# coaches.net
KiCad netlist of a schematic drawn in EAGLE
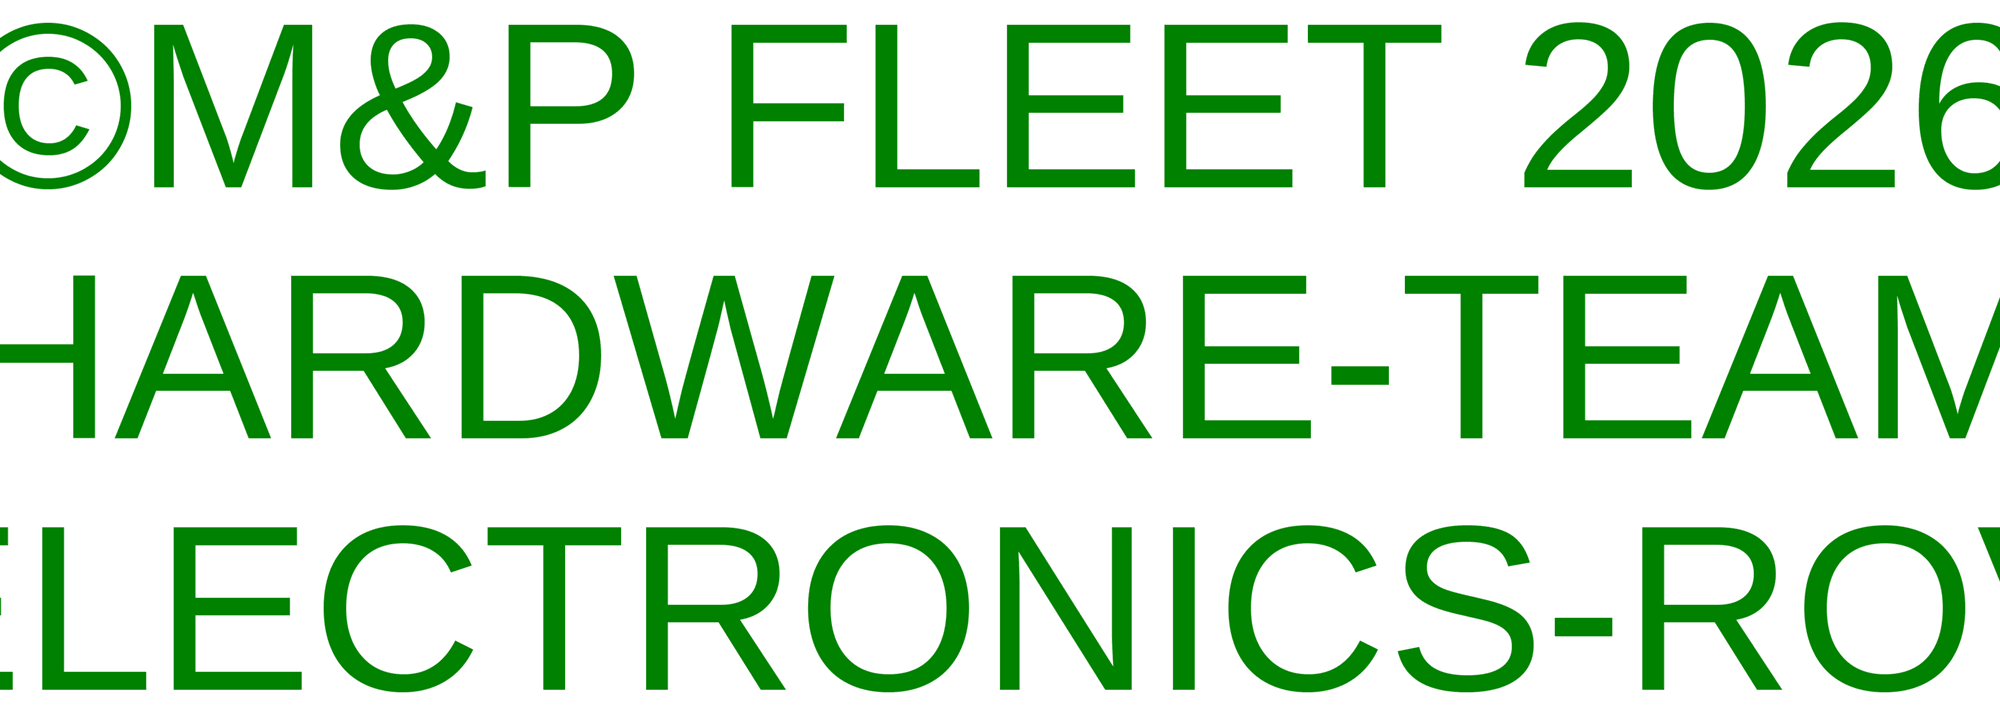
[diagram p0: schematic, sheet 1]
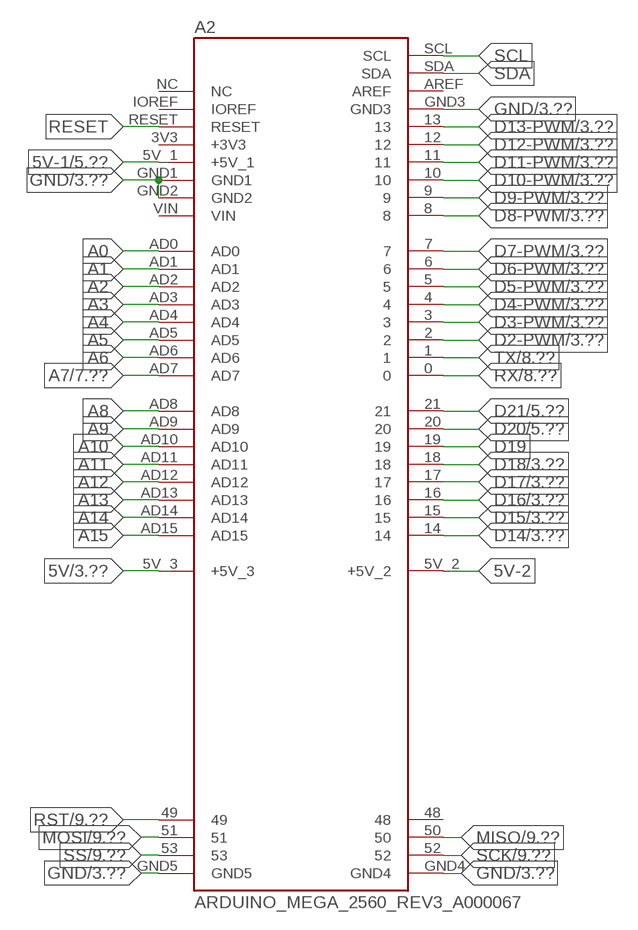
[diagram p1: schematic, sheet 2]
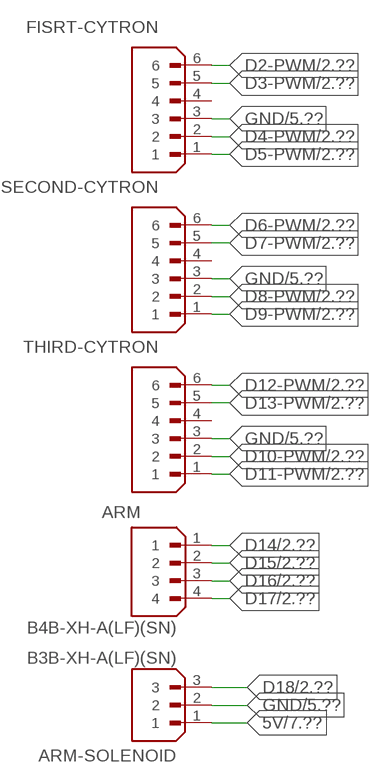
[diagram p2: schematic, sheet 3]
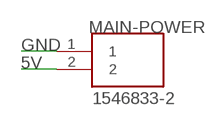
[diagram p3: schematic, sheet 4]
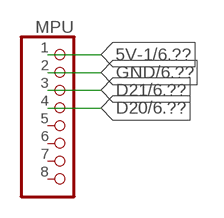
[diagram p4: schematic, sheet 5]
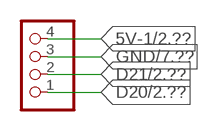
[diagram p5: schematic, sheet 6]
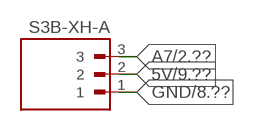
[diagram p6: schematic, sheet 7]
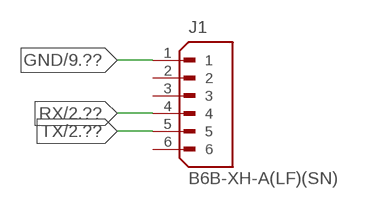
[diagram p7: schematic, sheet 8]
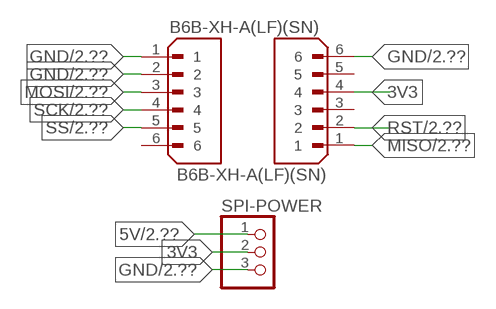
[diagram p8: schematic, sheet 9]

(export (version "E")
  (design (tool "Eeschema 10.0.6"))
  (components
    (comp (ref "A2")
      (value "ARDUINO_MEGA_2560_REV3_A000067")
      (footprint "eagle-import:ARDUINO_ARDUINO_MEGA_2560_REV3_A000067")
      (fields (field (name "MF") "Arduino") (field (name "MP") "ARDUINO MEGA 2560 REV3 | A000067"))
      (libsource (lib "eagle-import") (part "ARDUINO_MEGA_2560_REV3_A000067"))
    )
    (comp (ref "ARM")
      (value "B4B-XH-A(LF)(SN)")
      (footprint "eagle-import:JST_B4B-XH-A(LF)(SN)")
      (fields (field (name "MF") "JST Sales") (field (name "MP") "B4B-XH-A (LF)(SN)"))
      (libsource (lib "eagle-import") (part "B4B-XH-A(LF)(SN)"))
    )
    (comp (ref "ARM-SOLENOID")
      (value "B3B-XH-A(LF)(SN)")
      (footprint "eagle-import:JST_B3B-XH-A(LF)(SN)")
      (fields (field (name "MF") "JST Sales"))
      (libsource (lib "eagle-import") (part "B3B-XH-A(LF)(SN)"))
    )
    (comp (ref "FISRT-CYTRON")
      (value "B6B-XH-A(LF)(SN)")
      (footprint "eagle-import:JST_B6B-XH-A(LF)(SN)")
      (fields (field (name "MF") "JST Sales") (field (name "MP") "B6B-XH-A (LF)(SN)"))
      (libsource (lib "eagle-import") (part "data-cable(6-pin)_48447798_B6B-XH-A(LF)(SN)"))
    )
    (comp (ref "SECOND-CYTRON")
      (value "B6B-XH-A(LF)(SN)")
      (footprint "eagle-import:JST_B6B-XH-A(LF)(SN)")
      (fields (field (name "MF") "JST Sales") (field (name "MP") "B6B-XH-A (LF)(SN)"))
      (libsource (lib "eagle-import") (part "data-cable(6-pin)_48447798_B6B-XH-A(LF)(SN)"))
    )
    (comp (ref "THIRD-CYTRON")
      (value "B6B-XH-A(LF)(SN)")
      (footprint "eagle-import:JST_B6B-XH-A(LF)(SN)")
      (fields (field (name "MF") "JST Sales") (field (name "MP") "B6B-XH-A (LF)(SN)"))
      (libsource (lib "eagle-import") (part "data-cable(6-pin)_48447798_B6B-XH-A(LF)(SN)"))
    )
    (comp (ref "J2")
      (value "B6B-XH-A(LF)(SN)")
      (footprint "eagle-import:JST_B6B-XH-A(LF)(SN)")
      (fields (field (name "MF") "JST Sales") (field (name "MP") "B6B-XH-A (LF)(SN)"))
      (libsource (lib "eagle-import") (part "B6B-XH-A(LF)(SN)"))
    )
    (comp (ref "J4")
      (value "B6B-XH-A(LF)(SN)")
      (footprint "eagle-import:JST_B6B-XH-A(LF)(SN)")
      (fields (field (name "MF") "JST Sales") (field (name "MP") "B6B-XH-A (LF)(SN)"))
      (libsource (lib "eagle-import") (part "B6B-XH-A(LF)(SN)"))
    )
    (comp (ref "SPI-POWER")
      (value "PINHD-1X3")
      (footprint "eagle-import:1X03")
      (libsource (lib "eagle-import") (part "PINHD-1X3"))
    )
    (comp (ref "PROMETER")
      (value "PINHD-1X4")
      (footprint "eagle-import:1X04")
      (libsource (lib "eagle-import") (part "PINHD-1X4"))
    )
    (comp (ref "MAIN-POWER")
      (value "1546833-2")
      (footprint "eagle-import:TE_1546833-2")
      (fields (field (name "MF") "TE Connectivity"))
      (libsource (lib "eagle-import") (part "1546833-2"))
    )
    (comp (ref "J3")
      (value "S3B-XH-A")
      (footprint "eagle-import:JST_S3B-XH-A")
      (fields (field (name "MF") "JST"))
      (libsource (lib "eagle-import") (part "S3B-XH-A"))
    )
    (comp (ref "MPU")
      (value "PINHD-1X8")
      (footprint "eagle-import:1X08")
      (libsource (lib "eagle-import") (part "PINHD-1X8"))
    )
    (comp (ref "J1")
      (value "B6B-XH-A(LF)(SN)")
      (footprint "eagle-import:JST_B6B-XH-A(LF)(SN)")
      (fields (field (name "MF") "JST Sales") (field (name "MP") "B6B-XH-A (LF)(SN)"))
      (libsource (lib "eagle-import") (part "data-cable(6-pin)_48447798_B6B-XH-A(LF)(SN)"))
    )
  )
  (nets
    (net (code "1") (name "3V3") (class "Default")
      (node (ref "J4") (pin "4") (pinfunction "4_4") (pintype "passive"))
      (node (ref "SPI-POWER") (pin "2") (pinfunction "2_2") (pintype "passive"))
    )
    (net (code "2") (name "5V") (class "Default")
      (node (ref "A2") (pin "5V_3") (pinfunction "+5V_3_5V_3") (pintype "passive"))
      (node (ref "ARM-SOLENOID") (pin "1") (pinfunction "1_1") (pintype "passive"))
      (node (ref "J3") (pin "2") (pinfunction "2_2") (pintype "passive"))
      (node (ref "MAIN-POWER") (pin "2") (pinfunction "2_2") (pintype "passive"))
      (node (ref "SPI-POWER") (pin "1") (pinfunction "1_1") (pintype "passive"))
    )
    (net (code "3") (name "5V-1") (class "Default")
      (node (ref "A2") (pin "5V_1") (pinfunction "+5V_1_5V_1") (pintype "passive"))
      (node (ref "MPU") (pin "1") (pinfunction "1_1") (pintype "passive"))
      (node (ref "PROMETER") (pin "4") (pinfunction "4_4") (pintype "passive"))
    )
    (net (code "4") (name "5V-2") (class "Default")
      (node (ref "A2") (pin "5V_2") (pinfunction "+5V_2_5V_2") (pintype "passive"))
    )
    (net (code "5") (name "A0") (class "Default")
      (node (ref "A2") (pin "AD0") (pinfunction "AD0_AD0") (pintype "passive"))
    )
    (net (code "6") (name "A1") (class "Default")
      (node (ref "A2") (pin "AD1") (pinfunction "AD1_AD1") (pintype "passive"))
    )
    (net (code "7") (name "A2") (class "Default")
      (node (ref "A2") (pin "AD2") (pinfunction "AD2_AD2") (pintype "passive"))
    )
    (net (code "8") (name "A3") (class "Default")
      (node (ref "A2") (pin "AD3") (pinfunction "AD3_AD3") (pintype "passive"))
    )
    (net (code "9") (name "A4") (class "Default")
      (node (ref "A2") (pin "AD4") (pinfunction "AD4_AD4") (pintype "passive"))
    )
    (net (code "10") (name "A5") (class "Default")
      (node (ref "A2") (pin "AD5") (pinfunction "AD5_AD5") (pintype "passive"))
    )
    (net (code "11") (name "A6") (class "Default")
      (node (ref "A2") (pin "AD6") (pinfunction "AD6_AD6") (pintype "passive"))
    )
    (net (code "12") (name "A7") (class "Default")
      (node (ref "A2") (pin "AD7") (pinfunction "AD7_AD7") (pintype "passive"))
      (node (ref "J3") (pin "3") (pinfunction "3_3") (pintype "passive"))
    )
    (net (code "13") (name "A8") (class "Default")
      (node (ref "A2") (pin "AD8") (pinfunction "AD8_AD8") (pintype "passive"))
    )
    (net (code "14") (name "A9") (class "Default")
      (node (ref "A2") (pin "AD9") (pinfunction "AD9_AD9") (pintype "passive"))
    )
    (net (code "15") (name "A10") (class "Default")
      (node (ref "A2") (pin "AD10") (pinfunction "AD10_AD10") (pintype "passive"))
    )
    (net (code "16") (name "A11") (class "Default")
      (node (ref "A2") (pin "AD11") (pinfunction "AD11_AD11") (pintype "passive"))
    )
    (net (code "17") (name "A12") (class "Default")
      (node (ref "A2") (pin "AD12") (pinfunction "AD12_AD12") (pintype "passive"))
    )
    (net (code "18") (name "A13") (class "Default")
      (node (ref "A2") (pin "AD13") (pinfunction "AD13_AD13") (pintype "passive"))
    )
    (net (code "19") (name "A14") (class "Default")
      (node (ref "A2") (pin "AD14") (pinfunction "AD14_AD14") (pintype "passive"))
    )
    (net (code "20") (name "A15") (class "Default")
      (node (ref "A2") (pin "AD15") (pinfunction "AD15_AD15") (pintype "passive"))
    )
    (net (code "21") (name "D2-PWM") (class "Default")
      (node (ref "A2") (pin "2") (pinfunction "2_2") (pintype "passive"))
      (node (ref "FISRT-CYTRON") (pin "6") (pinfunction "6_6") (pintype "passive"))
    )
    (net (code "22") (name "D3-PWM") (class "Default")
      (node (ref "A2") (pin "3") (pinfunction "3_3") (pintype "passive"))
      (node (ref "FISRT-CYTRON") (pin "5") (pinfunction "5_5") (pintype "passive"))
    )
    (net (code "23") (name "D4-PWM") (class "Default")
      (node (ref "A2") (pin "4") (pinfunction "4_4") (pintype "passive"))
      (node (ref "FISRT-CYTRON") (pin "2") (pinfunction "2_2") (pintype "passive"))
    )
    (net (code "24") (name "D5-PWM") (class "Default")
      (node (ref "A2") (pin "5") (pinfunction "5_5") (pintype "passive"))
      (node (ref "FISRT-CYTRON") (pin "1") (pinfunction "1_1") (pintype "passive"))
    )
    (net (code "25") (name "D6-PWM") (class "Default")
      (node (ref "A2") (pin "6") (pinfunction "6_6") (pintype "passive"))
      (node (ref "SECOND-CYTRON") (pin "6") (pinfunction "6_6") (pintype "passive"))
    )
    (net (code "26") (name "D7-PWM") (class "Default")
      (node (ref "A2") (pin "7") (pinfunction "7_7") (pintype "passive"))
      (node (ref "SECOND-CYTRON") (pin "5") (pinfunction "5_5") (pintype "passive"))
    )
    (net (code "27") (name "D8-PWM") (class "Default")
      (node (ref "A2") (pin "8") (pinfunction "8_8") (pintype "passive"))
      (node (ref "SECOND-CYTRON") (pin "2") (pinfunction "2_2") (pintype "passive"))
    )
    (net (code "28") (name "D9-PWM") (class "Default")
      (node (ref "A2") (pin "9") (pinfunction "9_9") (pintype "passive"))
      (node (ref "SECOND-CYTRON") (pin "1") (pinfunction "1_1") (pintype "passive"))
    )
    (net (code "29") (name "D10-PWM") (class "Default")
      (node (ref "A2") (pin "10") (pinfunction "10_10") (pintype "passive"))
      (node (ref "THIRD-CYTRON") (pin "2") (pinfunction "2_2") (pintype "passive"))
    )
    (net (code "30") (name "D11-PWM") (class "Default")
      (node (ref "A2") (pin "11") (pinfunction "11_11") (pintype "passive"))
      (node (ref "THIRD-CYTRON") (pin "1") (pinfunction "1_1") (pintype "passive"))
    )
    (net (code "31") (name "D12-PWM") (class "Default")
      (node (ref "A2") (pin "12") (pinfunction "12_12") (pintype "passive"))
      (node (ref "THIRD-CYTRON") (pin "6") (pinfunction "6_6") (pintype "passive"))
    )
    (net (code "32") (name "D13-PWM") (class "Default")
      (node (ref "A2") (pin "13") (pinfunction "13_13") (pintype "passive"))
      (node (ref "THIRD-CYTRON") (pin "5") (pinfunction "5_5") (pintype "passive"))
    )
    (net (code "33") (name "D14") (class "Default")
      (node (ref "A2") (pin "14") (pinfunction "14_14") (pintype "passive"))
      (node (ref "ARM") (pin "1") (pinfunction "1_1") (pintype "passive"))
    )
    (net (code "34") (name "D15") (class "Default")
      (node (ref "A2") (pin "15") (pinfunction "15_15") (pintype "passive"))
      (node (ref "ARM") (pin "2") (pinfunction "2_2") (pintype "passive"))
    )
    (net (code "35") (name "D16") (class "Default")
      (node (ref "A2") (pin "16") (pinfunction "16_16") (pintype "passive"))
      (node (ref "ARM") (pin "3") (pinfunction "3_3") (pintype "passive"))
    )
    (net (code "36") (name "D17") (class "Default")
      (node (ref "A2") (pin "17") (pinfunction "17_17") (pintype "passive"))
      (node (ref "ARM") (pin "4") (pinfunction "4_4") (pintype "passive"))
    )
    (net (code "37") (name "D18") (class "Default")
      (node (ref "A2") (pin "18") (pinfunction "18_18") (pintype "passive"))
      (node (ref "ARM-SOLENOID") (pin "3") (pinfunction "3_3") (pintype "passive"))
    )
    (net (code "38") (name "D19") (class "Default")
      (node (ref "A2") (pin "19") (pinfunction "19_19") (pintype "passive"))
    )
    (net (code "39") (name "D20") (class "Default")
      (node (ref "A2") (pin "20") (pinfunction "20_20") (pintype "passive"))
      (node (ref "MPU") (pin "4") (pinfunction "4_4") (pintype "passive"))
      (node (ref "PROMETER") (pin "1") (pinfunction "1_1") (pintype "passive"))
    )
    (net (code "40") (name "D21") (class "Default")
      (node (ref "A2") (pin "21") (pinfunction "21_21") (pintype "passive"))
      (node (ref "MPU") (pin "3") (pinfunction "3_3") (pintype "passive"))
      (node (ref "PROMETER") (pin "2") (pinfunction "2_2") (pintype "passive"))
    )
    (net (code "41") (name "GND") (class "Default")
      (node (ref "A2") (pin "GND1") (pinfunction "GND1_GND1") (pintype "passive"))
      (node (ref "A2") (pin "GND2") (pinfunction "GND2_GND2") (pintype "passive"))
      (node (ref "A2") (pin "GND3") (pinfunction "GND3_GND3") (pintype "passive"))
      (node (ref "A2") (pin "GND4") (pinfunction "GND4_GND4") (pintype "passive"))
      (node (ref "A2") (pin "GND5") (pinfunction "GND5_GND5") (pintype "passive"))
      (node (ref "ARM-SOLENOID") (pin "2") (pinfunction "2_2") (pintype "passive"))
      (node (ref "FISRT-CYTRON") (pin "3") (pinfunction "3_3") (pintype "passive"))
      (node (ref "J1") (pin "1") (pinfunction "1_1") (pintype "passive"))
      (node (ref "J2") (pin "1") (pinfunction "1_1") (pintype "passive"))
      (node (ref "J2") (pin "2") (pinfunction "2_2") (pintype "passive"))
      (node (ref "J3") (pin "1") (pinfunction "1_1") (pintype "passive"))
      (node (ref "J4") (pin "6") (pinfunction "6_6") (pintype "passive"))
      (node (ref "MAIN-POWER") (pin "1") (pinfunction "1_1") (pintype "passive"))
      (node (ref "MPU") (pin "2") (pinfunction "2_2") (pintype "passive"))
      (node (ref "PROMETER") (pin "3") (pinfunction "3_3") (pintype "passive"))
      (node (ref "SECOND-CYTRON") (pin "3") (pinfunction "3_3") (pintype "passive"))
      (node (ref "SPI-POWER") (pin "3") (pinfunction "3_3") (pintype "passive"))
      (node (ref "THIRD-CYTRON") (pin "3") (pinfunction "3_3") (pintype "passive"))
    )
    (net (code "42") (name "MISO") (class "Default")
      (node (ref "A2") (pin "50") (pinfunction "50_50") (pintype "passive"))
      (node (ref "J4") (pin "1") (pinfunction "1_1") (pintype "passive"))
    )
    (net (code "43") (name "MOSI") (class "Default")
      (node (ref "A2") (pin "51") (pinfunction "51_51") (pintype "passive"))
      (node (ref "J2") (pin "3") (pinfunction "3_3") (pintype "passive"))
    )
    (net (code "44") (name "RESET") (class "Default")
      (node (ref "A2") (pin "RESET") (pinfunction "RESET_RESET") (pintype "passive"))
    )
    (net (code "45") (name "RST") (class "Default")
      (node (ref "A2") (pin "49") (pinfunction "49_49") (pintype "passive"))
      (node (ref "J4") (pin "2") (pinfunction "2_2") (pintype "passive"))
    )
    (net (code "46") (name "RX") (class "Default")
      (node (ref "A2") (pin "0") (pinfunction "0_0") (pintype "passive"))
      (node (ref "J1") (pin "4") (pinfunction "4_4") (pintype "passive"))
    )
    (net (code "47") (name "SCK") (class "Default")
      (node (ref "A2") (pin "52") (pinfunction "52_52") (pintype "passive"))
      (node (ref "J2") (pin "4") (pinfunction "4_4") (pintype "passive"))
    )
    (net (code "48") (name "SCL") (class "Default")
      (node (ref "A2") (pin "SCL") (pinfunction "SCL_SCL") (pintype "passive"))
    )
    (net (code "49") (name "SDA") (class "Default")
      (node (ref "A2") (pin "SDA") (pinfunction "SDA_SDA") (pintype "passive"))
    )
    (net (code "50") (name "SS") (class "Default")
      (node (ref "A2") (pin "53") (pinfunction "53_53") (pintype "passive"))
      (node (ref "J2") (pin "5") (pinfunction "5_5") (pintype "passive"))
    )
    (net (code "51") (name "TX") (class "Default")
      (node (ref "A2") (pin "1") (pinfunction "1_1") (pintype "passive"))
      (node (ref "J1") (pin "5") (pinfunction "5_5") (pintype "passive"))
    )
    (net (code "52") (name "unconnected-(A2-+3V3-Pad3V3)") (class "Default")
      (node (ref "A2") (pin "3V3") (pinfunction "+3V3_3V3") (pintype "passive"))
    )
    (net (code "53") (name "unconnected-(A2-Pad48)") (class "Default")
      (node (ref "A2") (pin "48") (pinfunction "48_48") (pintype "passive"))
    )
    (net (code "54") (name "unconnected-(A2-PadAREF)") (class "Default")
      (node (ref "A2") (pin "AREF") (pinfunction "AREF_AREF") (pintype "passive"))
    )
    (net (code "55") (name "unconnected-(A2-PadIOREF)") (class "Default")
      (node (ref "A2") (pin "IOREF") (pinfunction "IOREF_IOREF") (pintype "passive"))
    )
    (net (code "56") (name "unconnected-(A2-PadNC)") (class "Default")
      (node (ref "A2") (pin "NC") (pinfunction "NC_NC") (pintype "passive"))
    )
    (net (code "57") (name "unconnected-(A2-PadVIN)") (class "Default")
      (node (ref "A2") (pin "VIN") (pinfunction "VIN_VIN") (pintype "passive"))
    )
    (net (code "58") (name "unconnected-(FISRT-CYTRON-Pad4)") (class "Default")
      (node (ref "FISRT-CYTRON") (pin "4") (pinfunction "4_4") (pintype "passive"))
    )
    (net (code "59") (name "unconnected-(J1-Pad2)") (class "Default")
      (node (ref "J1") (pin "2") (pinfunction "2_2") (pintype "passive"))
    )
    (net (code "60") (name "unconnected-(J1-Pad3)") (class "Default")
      (node (ref "J1") (pin "3") (pinfunction "3_3") (pintype "passive"))
    )
    (net (code "61") (name "unconnected-(J1-Pad6)") (class "Default")
      (node (ref "J1") (pin "6") (pinfunction "6_6") (pintype "passive"))
    )
    (net (code "62") (name "unconnected-(J2-Pad6)") (class "Default")
      (node (ref "J2") (pin "6") (pinfunction "6_6") (pintype "passive"))
    )
    (net (code "63") (name "unconnected-(J4-Pad3)") (class "Default")
      (node (ref "J4") (pin "3") (pinfunction "3_3") (pintype "passive"))
    )
    (net (code "64") (name "unconnected-(J4-Pad5)") (class "Default")
      (node (ref "J4") (pin "5") (pinfunction "5_5") (pintype "passive"))
    )
    (net (code "65") (name "unconnected-(MPU-Pad5)") (class "Default")
      (node (ref "MPU") (pin "5") (pinfunction "5_5") (pintype "passive"))
    )
    (net (code "66") (name "unconnected-(MPU-Pad6)") (class "Default")
      (node (ref "MPU") (pin "6") (pinfunction "6_6") (pintype "passive"))
    )
    (net (code "67") (name "unconnected-(MPU-Pad7)") (class "Default")
      (node (ref "MPU") (pin "7") (pinfunction "7_7") (pintype "passive"))
    )
    (net (code "68") (name "unconnected-(MPU-Pad8)") (class "Default")
      (node (ref "MPU") (pin "8") (pinfunction "8_8") (pintype "passive"))
    )
    (net (code "69") (name "unconnected-(SECOND-CYTRON-Pad4)") (class "Default")
      (node (ref "SECOND-CYTRON") (pin "4") (pinfunction "4_4") (pintype "passive"))
    )
    (net (code "70") (name "unconnected-(THIRD-CYTRON-Pad4)") (class "Default")
      (node (ref "THIRD-CYTRON") (pin "4") (pinfunction "4_4") (pintype "passive"))
    )
  )
)
